# Connectors.net
KiCad netlist of a schematic drawn in Altium Designer
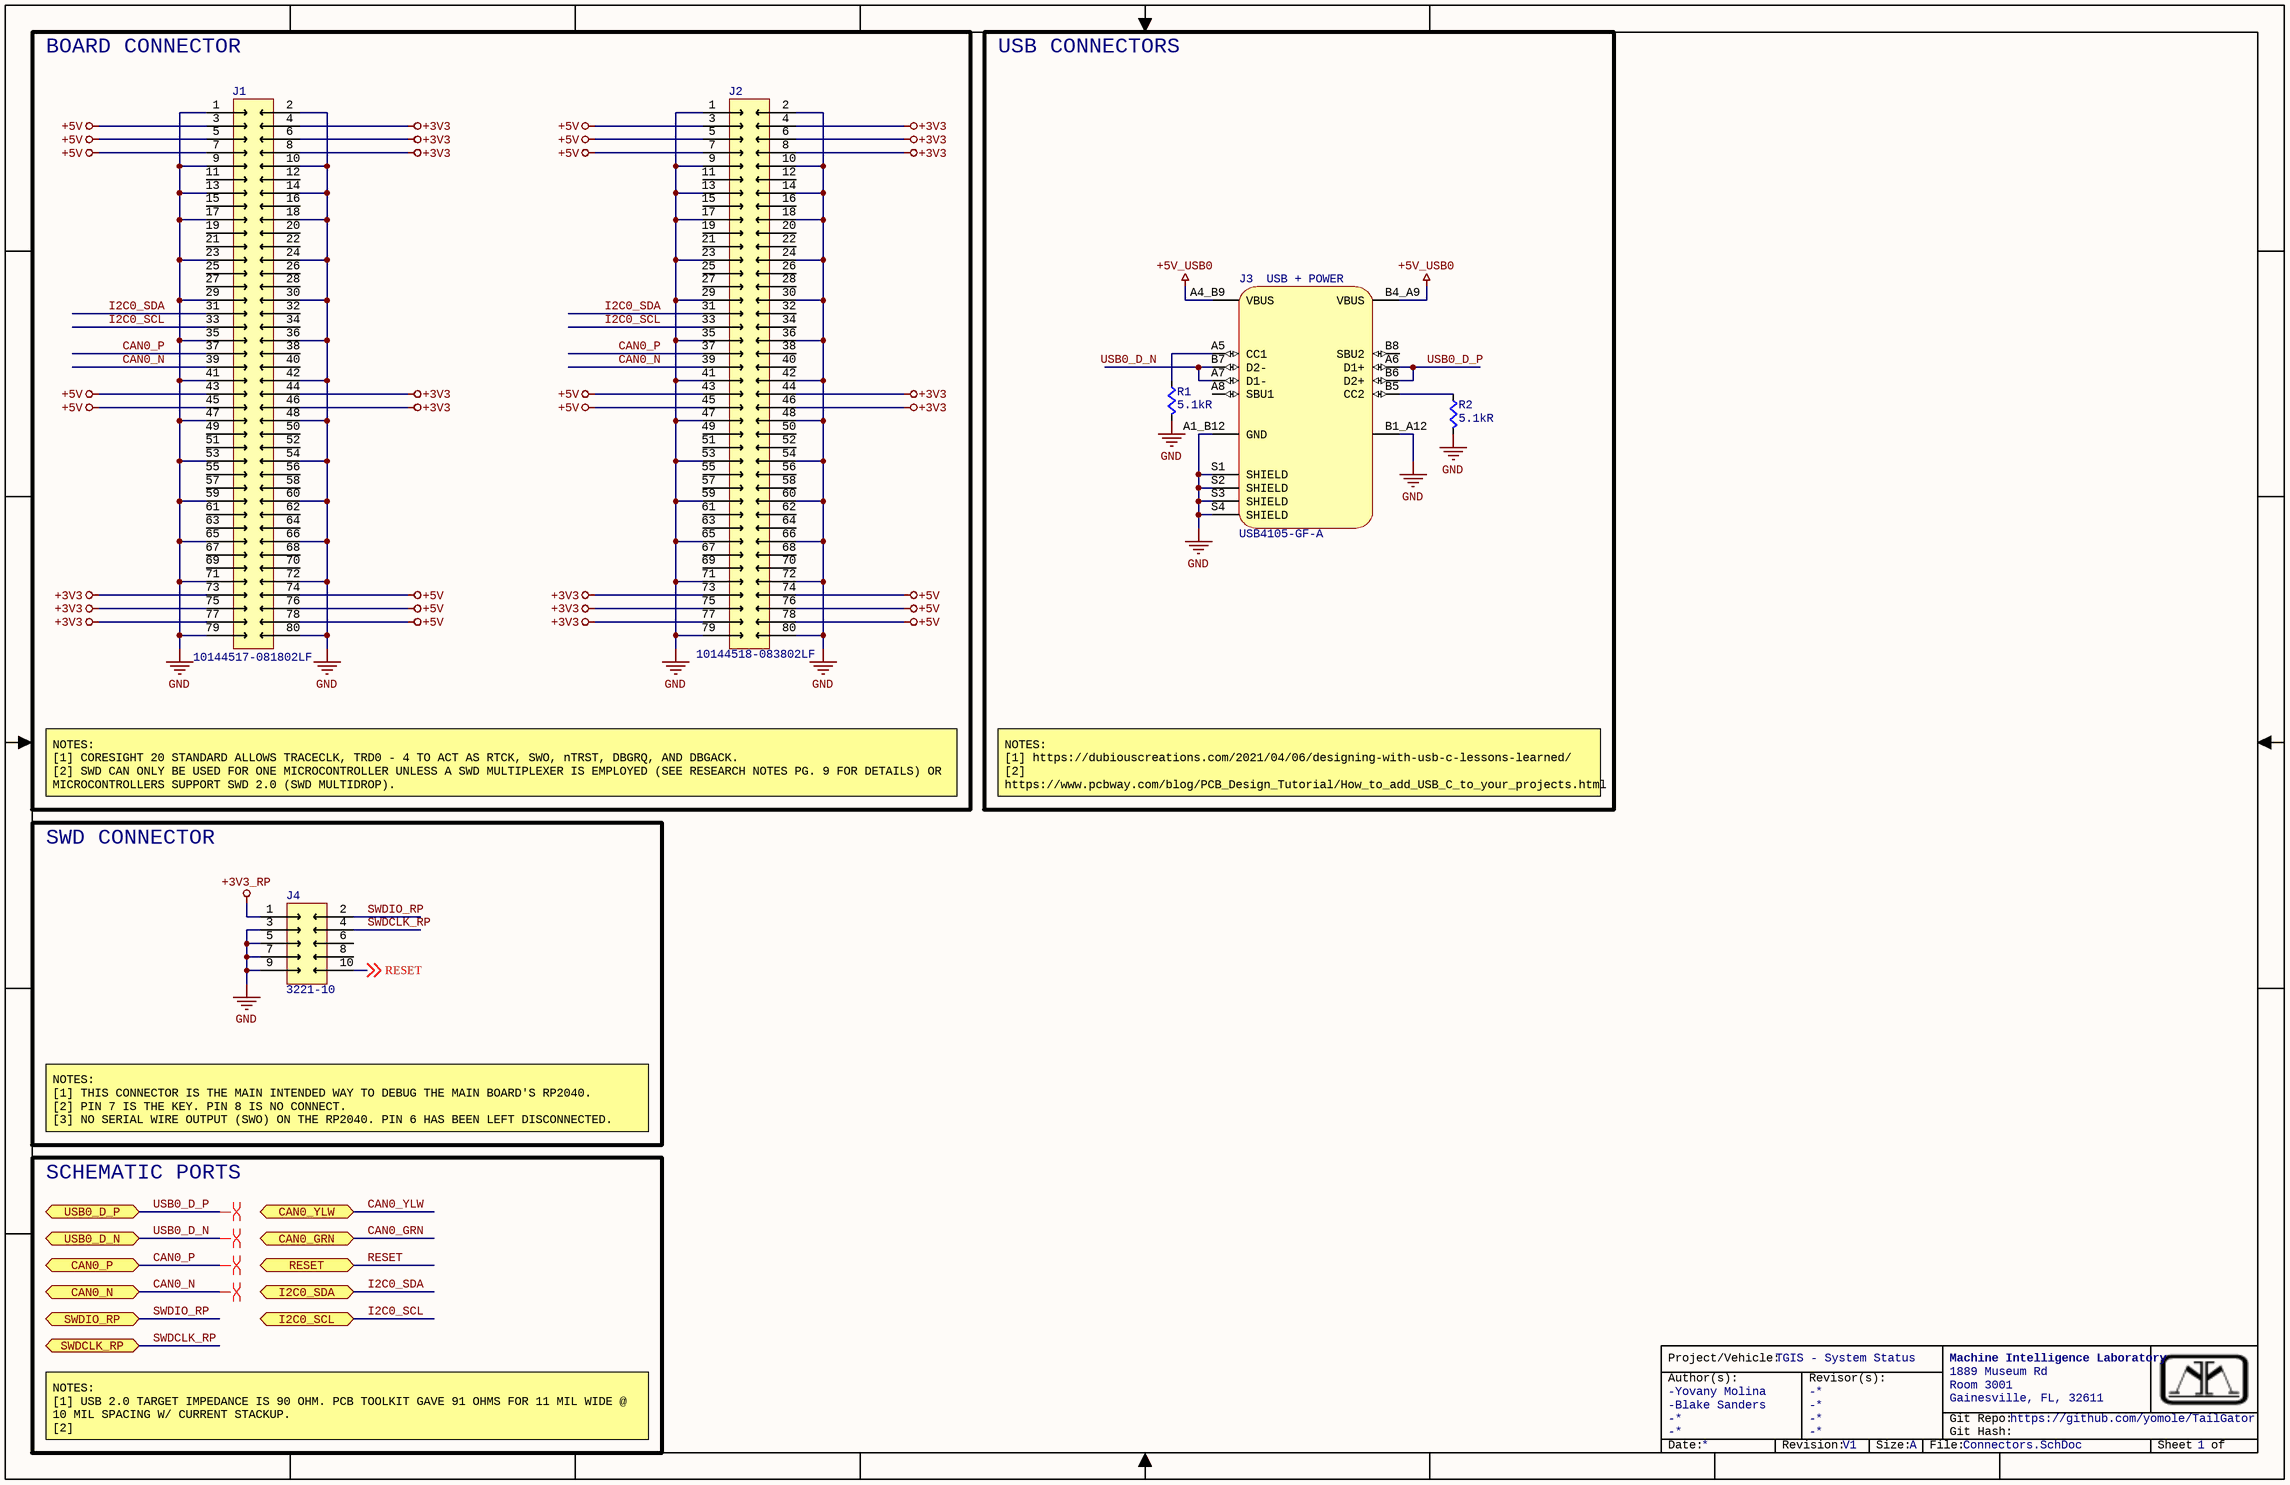
[diagram p0: Connectors.SchDoc]

(export (version "E")
  (design (tool "Eeschema 10.0.6"))
  (components
    (comp (ref "J1")
      (value "10144517-081802LF")
      (footprint "AMPHENOL_10144517-081802LF")
      (description "CONN RCPT 1 80POS SMD GOLD")
      (libsource (lib "TGIS") (part "10144517-081802LF"))
    )
    (comp (ref "J2")
      (value "10144518-083802LF")
      (footprint "AMPHENOL_10144518-083802LF")
      (description "CONN PLUG 3 80POS SMD GOLD")
      (libsource (lib "TGIS") (part "10144518-083802LF"))
    )
    (comp (ref "J3")
      (value "USB4105-GF-A")
      (footprint "GCT_USB4105-GF-A")
      (fields (field (name "MP") "USB4120-03-C_REVA"))
      (libsource (lib "TGIS") (part "USB4105-GF-A"))
    )
    (comp (ref "J4")
      (value "3221-10")
      (footprint "3220-10-0200-00")
      (description "Connector Header Surface Mount 10 position 0.050\" (1.27mm)")
      (libsource (lib "TGIS_Connectors") (part "3221-10-0300-00"))
    )
    (comp (ref "R1")
      (value "5.1kR")
      (footprint "RES0603")
      (description "Fixed Resistor, Metal Glaze/thick F")
      (fields (field (name "PART NUMBER") "RC0603FR-075K1L") (field (name "POWER") "100mW"))
      (libsource (lib "Parts") (part "Resistor"))
    )
    (comp (ref "R2")
      (value "5.1kR")
      (footprint "RES0603")
      (description "Fixed Resistor, Metal Glaze/thick F")
      (fields (field (name "PART NUMBER") "RC0603FR-075K1L") (field (name "POWER") "100mW"))
      (libsource (lib "Parts") (part "Resistor"))
    )
  )
  (nets
    (net (code "1") (name "+3V3") (class "Default")
      (node (ref "J1") (pin "4") (pinfunction "4_4") (pintype "passive"))
      (node (ref "J1") (pin "44") (pinfunction "44_44") (pintype "passive"))
      (node (ref "J1") (pin "46") (pinfunction "46_46") (pintype "passive"))
      (node (ref "J1") (pin "6") (pinfunction "6_6") (pintype "passive"))
      (node (ref "J1") (pin "73") (pinfunction "73_73") (pintype "passive"))
      (node (ref "J1") (pin "75") (pinfunction "75_75") (pintype "passive"))
      (node (ref "J1") (pin "77") (pinfunction "77_77") (pintype "passive"))
      (node (ref "J1") (pin "8") (pinfunction "8_8") (pintype "passive"))
      (node (ref "J2") (pin "4") (pinfunction "4_4") (pintype "passive"))
      (node (ref "J2") (pin "44") (pinfunction "44_44") (pintype "passive"))
      (node (ref "J2") (pin "46") (pinfunction "46_46") (pintype "passive"))
      (node (ref "J2") (pin "6") (pinfunction "6_6") (pintype "passive"))
      (node (ref "J2") (pin "73") (pinfunction "73_73") (pintype "passive"))
      (node (ref "J2") (pin "75") (pinfunction "75_75") (pintype "passive"))
      (node (ref "J2") (pin "77") (pinfunction "77_77") (pintype "passive"))
      (node (ref "J2") (pin "8") (pinfunction "8_8") (pintype "passive"))
    )
    (net (code "2") (name "+3V3_RP") (class "Default")
      (node (ref "J4") (pin "1") (pinfunction "1_1") (pintype "passive"))
    )
    (net (code "3") (name "+5V") (class "Default")
      (node (ref "J1") (pin "3") (pinfunction "3_3") (pintype "passive"))
      (node (ref "J1") (pin "43") (pinfunction "43_43") (pintype "passive"))
      (node (ref "J1") (pin "45") (pinfunction "45_45") (pintype "passive"))
      (node (ref "J1") (pin "5") (pinfunction "5_5") (pintype "passive"))
      (node (ref "J1") (pin "7") (pinfunction "7_7") (pintype "passive"))
      (node (ref "J1") (pin "74") (pinfunction "74_74") (pintype "passive"))
      (node (ref "J1") (pin "76") (pinfunction "76_76") (pintype "passive"))
      (node (ref "J1") (pin "78") (pinfunction "78_78") (pintype "passive"))
      (node (ref "J2") (pin "3") (pinfunction "3_3") (pintype "passive"))
      (node (ref "J2") (pin "43") (pinfunction "43_43") (pintype "passive"))
      (node (ref "J2") (pin "45") (pinfunction "45_45") (pintype "passive"))
      (node (ref "J2") (pin "5") (pinfunction "5_5") (pintype "passive"))
      (node (ref "J2") (pin "7") (pinfunction "7_7") (pintype "passive"))
      (node (ref "J2") (pin "74") (pinfunction "74_74") (pintype "passive"))
      (node (ref "J2") (pin "76") (pinfunction "76_76") (pintype "passive"))
      (node (ref "J2") (pin "78") (pinfunction "78_78") (pintype "passive"))
    )
    (net (code "4") (name "+5V_USB0") (class "Default")
      (node (ref "J3") (pin "A4_B9") (pinfunction "VBUS_A4_B9") (pintype "power_in"))
      (node (ref "J3") (pin "B4_A9") (pinfunction "VBUS_B4_A9") (pintype "power_in"))
    )
    (net (code "6") (name "/CAN0_N") (class "Default")
      (node (ref "J1") (pin "39") (pinfunction "39_39") (pintype "passive"))
      (node (ref "J2") (pin "39") (pinfunction "39_39") (pintype "passive"))
    )
    (net (code "7") (name "/CAN0_P") (class "Default")
      (node (ref "J1") (pin "37") (pinfunction "37_37") (pintype "passive"))
      (node (ref "J2") (pin "37") (pinfunction "37_37") (pintype "passive"))
    )
    (net (code "9") (name "/I2C0_SCL") (class "Default")
      (node (ref "J1") (pin "33") (pinfunction "33_33") (pintype "passive"))
      (node (ref "J2") (pin "33") (pinfunction "33_33") (pintype "passive"))
    )
    (net (code "10") (name "/I2C0_SDA") (class "Default")
      (node (ref "J1") (pin "31") (pinfunction "31_31") (pintype "passive"))
      (node (ref "J2") (pin "31") (pinfunction "31_31") (pintype "passive"))
    )
    (net (code "11") (name "/SWDCLK_RP") (class "Default")
      (node (ref "J4") (pin "4") (pinfunction "4_4") (pintype "passive"))
    )
    (net (code "12") (name "/SWDIO_RP") (class "Default")
      (node (ref "J4") (pin "2") (pinfunction "2_2") (pintype "passive"))
    )
    (net (code "13") (name "/USB0_D_N") (class "Default")
      (node (ref "J3") (pin "A7") (pinfunction "D1-_A7") (pintype "bidirectional"))
      (node (ref "J3") (pin "B7") (pinfunction "D2-_B7") (pintype "bidirectional"))
    )
    (net (code "14") (name "/USB0_D_P") (class "Default")
      (node (ref "J3") (pin "A6") (pinfunction "D1+_A6") (pintype "bidirectional"))
      (node (ref "J3") (pin "B6") (pinfunction "D2+_B6") (pintype "bidirectional"))
    )
    (net (code "15") (name "GND") (class "Default")
      (node (ref "J1") (pin "1") (pinfunction "1_1") (pintype "passive"))
      (node (ref "J1") (pin "10") (pinfunction "10_10") (pintype "passive"))
      (node (ref "J1") (pin "13") (pinfunction "13_13") (pintype "passive"))
      (node (ref "J1") (pin "14") (pinfunction "14_14") (pintype "passive"))
      (node (ref "J1") (pin "17") (pinfunction "17_17") (pintype "passive"))
      (node (ref "J1") (pin "18") (pinfunction "18_18") (pintype "passive"))
      (node (ref "J1") (pin "2") (pinfunction "2_2") (pintype "passive"))
      (node (ref "J1") (pin "23") (pinfunction "23_23") (pintype "passive"))
      (node (ref "J1") (pin "24") (pinfunction "24_24") (pintype "passive"))
      (node (ref "J1") (pin "29") (pinfunction "29_29") (pintype "passive"))
      (node (ref "J1") (pin "30") (pinfunction "30_30") (pintype "passive"))
      (node (ref "J1") (pin "35") (pinfunction "35_35") (pintype "passive"))
      (node (ref "J1") (pin "36") (pinfunction "36_36") (pintype "passive"))
      (node (ref "J1") (pin "41") (pinfunction "41_41") (pintype "passive"))
      (node (ref "J1") (pin "42") (pinfunction "42_42") (pintype "passive"))
      (node (ref "J1") (pin "47") (pinfunction "47_47") (pintype "passive"))
      (node (ref "J1") (pin "48") (pinfunction "48_48") (pintype "passive"))
      (node (ref "J1") (pin "53") (pinfunction "53_53") (pintype "passive"))
      (node (ref "J1") (pin "54") (pinfunction "54_54") (pintype "passive"))
      (node (ref "J1") (pin "59") (pinfunction "59_59") (pintype "passive"))
      (node (ref "J1") (pin "60") (pinfunction "60_60") (pintype "passive"))
      (node (ref "J1") (pin "65") (pinfunction "65_65") (pintype "passive"))
      (node (ref "J1") (pin "66") (pinfunction "66_66") (pintype "passive"))
      (node (ref "J1") (pin "71") (pinfunction "71_71") (pintype "passive"))
      (node (ref "J1") (pin "72") (pinfunction "72_72") (pintype "passive"))
      (node (ref "J1") (pin "79") (pinfunction "79_79") (pintype "passive"))
      (node (ref "J1") (pin "80") (pinfunction "80_80") (pintype "passive"))
      (node (ref "J1") (pin "9") (pinfunction "9_9") (pintype "passive"))
      (node (ref "J2") (pin "1") (pinfunction "1_1") (pintype "passive"))
      (node (ref "J2") (pin "10") (pinfunction "10_10") (pintype "passive"))
      (node (ref "J2") (pin "13") (pinfunction "13_13") (pintype "passive"))
      (node (ref "J2") (pin "14") (pinfunction "14_14") (pintype "passive"))
      (node (ref "J2") (pin "17") (pinfunction "17_17") (pintype "passive"))
      (node (ref "J2") (pin "18") (pinfunction "18_18") (pintype "passive"))
      (node (ref "J2") (pin "2") (pinfunction "2_2") (pintype "passive"))
      (node (ref "J2") (pin "23") (pinfunction "23_23") (pintype "passive"))
      (node (ref "J2") (pin "24") (pinfunction "24_24") (pintype "passive"))
      (node (ref "J2") (pin "29") (pinfunction "29_29") (pintype "passive"))
      (node (ref "J2") (pin "30") (pinfunction "30_30") (pintype "passive"))
      (node (ref "J2") (pin "35") (pinfunction "35_35") (pintype "passive"))
      (node (ref "J2") (pin "36") (pinfunction "36_36") (pintype "passive"))
      (node (ref "J2") (pin "41") (pinfunction "41_41") (pintype "passive"))
      (node (ref "J2") (pin "42") (pinfunction "42_42") (pintype "passive"))
      (node (ref "J2") (pin "47") (pinfunction "47_47") (pintype "passive"))
      (node (ref "J2") (pin "48") (pinfunction "48_48") (pintype "passive"))
      (node (ref "J2") (pin "53") (pinfunction "53_53") (pintype "passive"))
      (node (ref "J2") (pin "54") (pinfunction "54_54") (pintype "passive"))
      (node (ref "J2") (pin "59") (pinfunction "59_59") (pintype "passive"))
      (node (ref "J2") (pin "60") (pinfunction "60_60") (pintype "passive"))
      (node (ref "J2") (pin "65") (pinfunction "65_65") (pintype "passive"))
      (node (ref "J2") (pin "66") (pinfunction "66_66") (pintype "passive"))
      (node (ref "J2") (pin "71") (pinfunction "71_71") (pintype "passive"))
      (node (ref "J2") (pin "72") (pinfunction "72_72") (pintype "passive"))
      (node (ref "J2") (pin "79") (pinfunction "79_79") (pintype "passive"))
      (node (ref "J2") (pin "80") (pinfunction "80_80") (pintype "passive"))
      (node (ref "J2") (pin "9") (pinfunction "9_9") (pintype "passive"))
      (node (ref "J3") (pin "A1_B12") (pinfunction "GND_A1_B12") (pintype "power_in"))
      (node (ref "J3") (pin "B1_A12") (pintype "power_in"))
      (node (ref "J3") (pin "S1") (pinfunction "SHIELD_S1") (pintype "passive"))
      (node (ref "J3") (pin "S2") (pinfunction "SHIELD_S2") (pintype "passive"))
      (node (ref "J3") (pin "S3") (pinfunction "SHIELD_S3") (pintype "passive"))
      (node (ref "J3") (pin "S4") (pinfunction "SHIELD_S4") (pintype "passive"))
      (node (ref "J4") (pin "3") (pinfunction "3_3") (pintype "passive"))
      (node (ref "J4") (pin "5") (pinfunction "5_5") (pintype "passive"))
      (node (ref "J4") (pin "7") (pinfunction "7_7") (pintype "passive"))
      (node (ref "J4") (pin "9") (pinfunction "9_9") (pintype "passive"))
      (node (ref "R1") (pin "1") (pinfunction "A_1") (pintype "passive"))
      (node (ref "R2") (pin "1") (pinfunction "A_1") (pintype "passive"))
    )
    (net (code "16") (name "Net-(J3-CC1)") (class "Default")
      (node (ref "J3") (pin "A5") (pinfunction "CC1_A5") (pintype "bidirectional"))
      (node (ref "R1") (pin "2") (pinfunction "B_2") (pintype "passive"))
    )
    (net (code "17") (name "Net-(J3-CC2)") (class "Default")
      (node (ref "J3") (pin "B5") (pinfunction "CC2_B5") (pintype "bidirectional"))
      (node (ref "R2") (pin "2") (pinfunction "B_2") (pintype "passive"))
    )
    (net (code "18") (name "RESET") (class "Default")
      (node (ref "J4") (pin "10") (pinfunction "10_10") (pintype "passive"))
    )
    (net (code "19") (name "unconnected-(J1-Pad11)") (class "Default")
      (node (ref "J1") (pin "11") (pinfunction "11_11") (pintype "passive"))
    )
    (net (code "20") (name "unconnected-(J1-Pad12)") (class "Default")
      (node (ref "J1") (pin "12") (pinfunction "12_12") (pintype "passive"))
    )
    (net (code "21") (name "unconnected-(J1-Pad15)") (class "Default")
      (node (ref "J1") (pin "15") (pinfunction "15_15") (pintype "passive"))
    )
    (net (code "22") (name "unconnected-(J1-Pad16)") (class "Default")
      (node (ref "J1") (pin "16") (pinfunction "16_16") (pintype "passive"))
    )
    (net (code "23") (name "unconnected-(J1-Pad19)") (class "Default")
      (node (ref "J1") (pin "19") (pinfunction "19_19") (pintype "passive"))
    )
    (net (code "24") (name "unconnected-(J1-Pad20)") (class "Default")
      (node (ref "J1") (pin "20") (pinfunction "20_20") (pintype "passive"))
    )
    (net (code "25") (name "unconnected-(J1-Pad21)") (class "Default")
      (node (ref "J1") (pin "21") (pinfunction "21_21") (pintype "passive"))
    )
    (net (code "26") (name "unconnected-(J1-Pad22)") (class "Default")
      (node (ref "J1") (pin "22") (pinfunction "22_22") (pintype "passive"))
    )
    (net (code "27") (name "unconnected-(J1-Pad25)") (class "Default")
      (node (ref "J1") (pin "25") (pinfunction "25_25") (pintype "passive"))
    )
    (net (code "28") (name "unconnected-(J1-Pad26)") (class "Default")
      (node (ref "J1") (pin "26") (pinfunction "26_26") (pintype "passive"))
    )
    (net (code "29") (name "unconnected-(J1-Pad27)") (class "Default")
      (node (ref "J1") (pin "27") (pinfunction "27_27") (pintype "passive"))
    )
    (net (code "30") (name "unconnected-(J1-Pad28)") (class "Default")
      (node (ref "J1") (pin "28") (pinfunction "28_28") (pintype "passive"))
    )
    (net (code "31") (name "unconnected-(J1-Pad32)") (class "Default")
      (node (ref "J1") (pin "32") (pinfunction "32_32") (pintype "passive"))
    )
    (net (code "32") (name "unconnected-(J1-Pad34)") (class "Default")
      (node (ref "J1") (pin "34") (pinfunction "34_34") (pintype "passive"))
    )
    (net (code "33") (name "unconnected-(J1-Pad38)") (class "Default")
      (node (ref "J1") (pin "38") (pinfunction "38_38") (pintype "passive"))
    )
    (net (code "34") (name "unconnected-(J1-Pad40)") (class "Default")
      (node (ref "J1") (pin "40") (pinfunction "40_40") (pintype "passive"))
    )
    (net (code "35") (name "unconnected-(J1-Pad49)") (class "Default")
      (node (ref "J1") (pin "49") (pinfunction "49_49") (pintype "passive"))
    )
    (net (code "36") (name "unconnected-(J1-Pad50)") (class "Default")
      (node (ref "J1") (pin "50") (pinfunction "50_50") (pintype "passive"))
    )
    (net (code "37") (name "unconnected-(J1-Pad51)") (class "Default")
      (node (ref "J1") (pin "51") (pinfunction "51_51") (pintype "passive"))
    )
    (net (code "38") (name "unconnected-(J1-Pad52)") (class "Default")
      (node (ref "J1") (pin "52") (pinfunction "52_52") (pintype "passive"))
    )
    (net (code "39") (name "unconnected-(J1-Pad55)") (class "Default")
      (node (ref "J1") (pin "55") (pinfunction "55_55") (pintype "passive"))
    )
    (net (code "40") (name "unconnected-(J1-Pad56)") (class "Default")
      (node (ref "J1") (pin "56") (pinfunction "56_56") (pintype "passive"))
    )
    (net (code "41") (name "unconnected-(J1-Pad57)") (class "Default")
      (node (ref "J1") (pin "57") (pinfunction "57_57") (pintype "passive"))
    )
    (net (code "42") (name "unconnected-(J1-Pad58)") (class "Default")
      (node (ref "J1") (pin "58") (pinfunction "58_58") (pintype "passive"))
    )
    (net (code "43") (name "unconnected-(J1-Pad61)") (class "Default")
      (node (ref "J1") (pin "61") (pinfunction "61_61") (pintype "passive"))
    )
    (net (code "44") (name "unconnected-(J1-Pad62)") (class "Default")
      (node (ref "J1") (pin "62") (pinfunction "62_62") (pintype "passive"))
    )
    (net (code "45") (name "unconnected-(J1-Pad63)") (class "Default")
      (node (ref "J1") (pin "63") (pinfunction "63_63") (pintype "passive"))
    )
    (net (code "46") (name "unconnected-(J1-Pad64)") (class "Default")
      (node (ref "J1") (pin "64") (pinfunction "64_64") (pintype "passive"))
    )
    (net (code "47") (name "unconnected-(J1-Pad67)") (class "Default")
      (node (ref "J1") (pin "67") (pinfunction "67_67") (pintype "passive"))
    )
    (net (code "48") (name "unconnected-(J1-Pad68)") (class "Default")
      (node (ref "J1") (pin "68") (pinfunction "68_68") (pintype "passive"))
    )
    (net (code "49") (name "unconnected-(J1-Pad69)") (class "Default")
      (node (ref "J1") (pin "69") (pinfunction "69_69") (pintype "passive"))
    )
    (net (code "50") (name "unconnected-(J1-Pad70)") (class "Default")
      (node (ref "J1") (pin "70") (pinfunction "70_70") (pintype "passive"))
    )
    (net (code "51") (name "unconnected-(J2-Pad11)") (class "Default")
      (node (ref "J2") (pin "11") (pinfunction "11_11") (pintype "passive"))
    )
    (net (code "52") (name "unconnected-(J2-Pad12)") (class "Default")
      (node (ref "J2") (pin "12") (pinfunction "12_12") (pintype "passive"))
    )
    (net (code "53") (name "unconnected-(J2-Pad15)") (class "Default")
      (node (ref "J2") (pin "15") (pinfunction "15_15") (pintype "passive"))
    )
    (net (code "54") (name "unconnected-(J2-Pad16)") (class "Default")
      (node (ref "J2") (pin "16") (pinfunction "16_16") (pintype "passive"))
    )
    (net (code "55") (name "unconnected-(J2-Pad19)") (class "Default")
      (node (ref "J2") (pin "19") (pinfunction "19_19") (pintype "passive"))
    )
    (net (code "56") (name "unconnected-(J2-Pad20)") (class "Default")
      (node (ref "J2") (pin "20") (pinfunction "20_20") (pintype "passive"))
    )
    (net (code "57") (name "unconnected-(J2-Pad21)") (class "Default")
      (node (ref "J2") (pin "21") (pinfunction "21_21") (pintype "passive"))
    )
    (net (code "58") (name "unconnected-(J2-Pad22)") (class "Default")
      (node (ref "J2") (pin "22") (pinfunction "22_22") (pintype "passive"))
    )
    (net (code "59") (name "unconnected-(J2-Pad25)") (class "Default")
      (node (ref "J2") (pin "25") (pinfunction "25_25") (pintype "passive"))
    )
    (net (code "60") (name "unconnected-(J2-Pad26)") (class "Default")
      (node (ref "J2") (pin "26") (pinfunction "26_26") (pintype "passive"))
    )
    (net (code "61") (name "unconnected-(J2-Pad27)") (class "Default")
      (node (ref "J2") (pin "27") (pinfunction "27_27") (pintype "passive"))
    )
    (net (code "62") (name "unconnected-(J2-Pad28)") (class "Default")
      (node (ref "J2") (pin "28") (pinfunction "28_28") (pintype "passive"))
    )
    (net (code "63") (name "unconnected-(J2-Pad32)") (class "Default")
      (node (ref "J2") (pin "32") (pinfunction "32_32") (pintype "passive"))
    )
    (net (code "64") (name "unconnected-(J2-Pad34)") (class "Default")
      (node (ref "J2") (pin "34") (pinfunction "34_34") (pintype "passive"))
    )
    (net (code "65") (name "unconnected-(J2-Pad38)") (class "Default")
      (node (ref "J2") (pin "38") (pinfunction "38_38") (pintype "passive"))
    )
    (net (code "66") (name "unconnected-(J2-Pad40)") (class "Default")
      (node (ref "J2") (pin "40") (pinfunction "40_40") (pintype "passive"))
    )
    (net (code "67") (name "unconnected-(J2-Pad49)") (class "Default")
      (node (ref "J2") (pin "49") (pinfunction "49_49") (pintype "passive"))
    )
    (net (code "68") (name "unconnected-(J2-Pad50)") (class "Default")
      (node (ref "J2") (pin "50") (pinfunction "50_50") (pintype "passive"))
    )
    (net (code "69") (name "unconnected-(J2-Pad51)") (class "Default")
      (node (ref "J2") (pin "51") (pinfunction "51_51") (pintype "passive"))
    )
    (net (code "70") (name "unconnected-(J2-Pad52)") (class "Default")
      (node (ref "J2") (pin "52") (pinfunction "52_52") (pintype "passive"))
    )
    (net (code "71") (name "unconnected-(J2-Pad55)") (class "Default")
      (node (ref "J2") (pin "55") (pinfunction "55_55") (pintype "passive"))
    )
    (net (code "72") (name "unconnected-(J2-Pad56)") (class "Default")
      (node (ref "J2") (pin "56") (pinfunction "56_56") (pintype "passive"))
    )
    (net (code "73") (name "unconnected-(J2-Pad57)") (class "Default")
      (node (ref "J2") (pin "57") (pinfunction "57_57") (pintype "passive"))
    )
    (net (code "74") (name "unconnected-(J2-Pad58)") (class "Default")
      (node (ref "J2") (pin "58") (pinfunction "58_58") (pintype "passive"))
    )
    (net (code "75") (name "unconnected-(J2-Pad61)") (class "Default")
      (node (ref "J2") (pin "61") (pinfunction "61_61") (pintype "passive"))
    )
    (net (code "76") (name "unconnected-(J2-Pad62)") (class "Default")
      (node (ref "J2") (pin "62") (pinfunction "62_62") (pintype "passive"))
    )
    (net (code "77") (name "unconnected-(J2-Pad63)") (class "Default")
      (node (ref "J2") (pin "63") (pinfunction "63_63") (pintype "passive"))
    )
    (net (code "78") (name "unconnected-(J2-Pad64)") (class "Default")
      (node (ref "J2") (pin "64") (pinfunction "64_64") (pintype "passive"))
    )
    (net (code "79") (name "unconnected-(J2-Pad67)") (class "Default")
      (node (ref "J2") (pin "67") (pinfunction "67_67") (pintype "passive"))
    )
    (net (code "80") (name "unconnected-(J2-Pad68)") (class "Default")
      (node (ref "J2") (pin "68") (pinfunction "68_68") (pintype "passive"))
    )
    (net (code "81") (name "unconnected-(J2-Pad69)") (class "Default")
      (node (ref "J2") (pin "69") (pinfunction "69_69") (pintype "passive"))
    )
    (net (code "82") (name "unconnected-(J2-Pad70)") (class "Default")
      (node (ref "J2") (pin "70") (pinfunction "70_70") (pintype "passive"))
    )
    (net (code "83") (name "unconnected-(J3-SBU1-PadA8)") (class "Default")
      (node (ref "J3") (pin "A8") (pinfunction "SBU1_A8") (pintype "bidirectional"))
    )
    (net (code "84") (name "unconnected-(J3-SBU2-PadB8)") (class "Default")
      (node (ref "J3") (pin "B8") (pinfunction "SBU2_B8") (pintype "bidirectional"))
    )
    (net (code "85") (name "unconnected-(J4-Pad6)") (class "Default")
      (node (ref "J4") (pin "6") (pinfunction "6_6") (pintype "passive"))
    )
    (net (code "86") (name "unconnected-(J4-Pad8)") (class "Default")
      (node (ref "J4") (pin "8") (pinfunction "8_8") (pintype "passive"))
    )
  )
)
